# HoverGames_v2.net
KiCad netlist of a schematic drawn in EAGLE
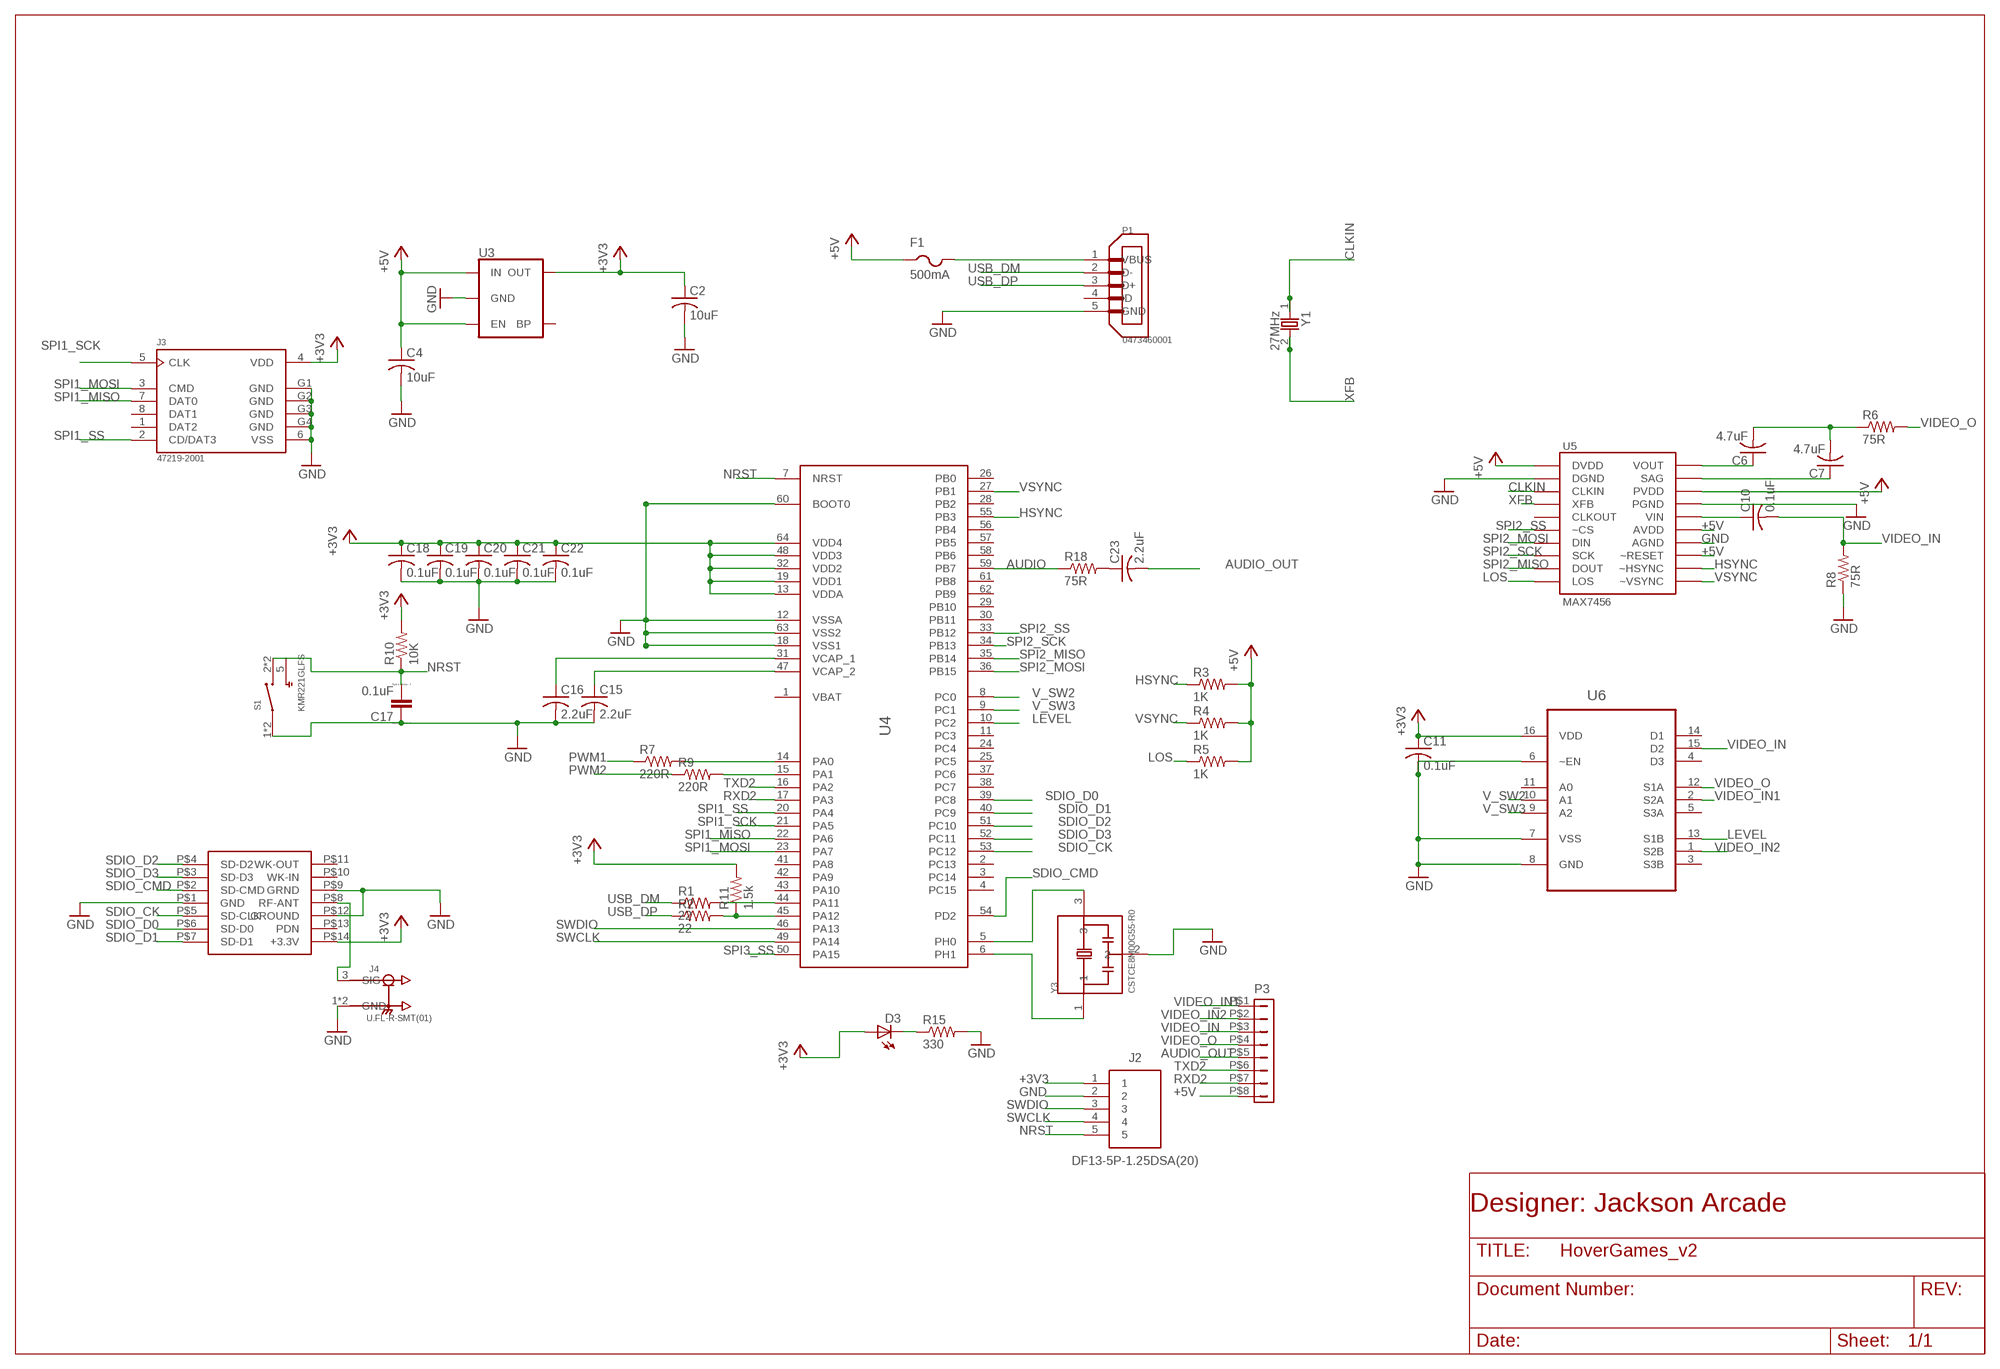
[diagram p0: schematic, sheet 1]

(export (version "E")
  (design (tool "Eeschema 10.0.6"))
  (components
    (comp (ref "C2")
      (value "10uF")
      (footprint "eagle-import:C0402")
      (libsource (lib "eagle-import") (part "C-USC0402"))
    )
    (comp (ref "C4")
      (value "10uF")
      (footprint "eagle-import:C0402")
      (libsource (lib "eagle-import") (part "C-USC0402"))
    )
    (comp (ref "C6")
      (value "4.7uF")
      (footprint "eagle-import:C0402")
      (libsource (lib "eagle-import") (part "C-USC0402"))
    )
    (comp (ref "C7")
      (value "4.7uF")
      (footprint "eagle-import:C0402")
      (libsource (lib "eagle-import") (part "C-USC0402"))
    )
    (comp (ref "C10")
      (value "0.1uF")
      (footprint "eagle-import:C0402")
      (libsource (lib "eagle-import") (part "resistor_348_C-USC0402"))
    )
    (comp (ref "C11")
      (value "0.1uF")
      (footprint "eagle-import:C0402")
      (libsource (lib "eagle-import") (part "C-USC0402"))
    )
    (comp (ref "C15")
      (value "2.2uF")
      (footprint "eagle-import:C0603")
      (libsource (lib "eagle-import") (part "C-USC0603"))
    )
    (comp (ref "C16")
      (value "2.2uF")
      (footprint "eagle-import:C0603")
      (libsource (lib "eagle-import") (part "C-USC0603"))
    )
    (comp (ref "C17")
      (value "0.1uF")
      (footprint "eagle-import:C0402")
      (libsource (lib "eagle-import") (part "CC0402"))
    )
    (comp (ref "C18")
      (value "0.1uF")
      (footprint "eagle-import:C0402")
      (libsource (lib "eagle-import") (part "C-USC0402"))
    )
    (comp (ref "C19")
      (value "0.1uF")
      (footprint "eagle-import:C0402")
      (libsource (lib "eagle-import") (part "C-USC0402"))
    )
    (comp (ref "C20")
      (value "0.1uF")
      (footprint "eagle-import:C0402")
      (libsource (lib "eagle-import") (part "C-USC0402"))
    )
    (comp (ref "C21")
      (value "0.1uF")
      (footprint "eagle-import:C0402")
      (libsource (lib "eagle-import") (part "C-USC0402"))
    )
    (comp (ref "C22")
      (value "0.1uF")
      (footprint "eagle-import:C0402")
      (libsource (lib "eagle-import") (part "C-USC0402"))
    )
    (comp (ref "C23")
      (value "2.2uF")
      (footprint "eagle-import:C0603")
      (libsource (lib "eagle-import") (part "C-USC0603"))
    )
    (comp (ref "D3")
      (value "LEDCHIP-LED0603")
      (footprint "eagle-import:CHIP-LED0603")
      (libsource (lib "eagle-import") (part "LEDCHIP-LED0603"))
    )
    (comp (ref "F1")
      (value "500mA")
      (footprint "eagle-import:R1206")
      (libsource (lib "eagle-import") (part "PTCFUSE-1206"))
    )
    (comp (ref "J2")
      (value "DF13-5P-1.25DSA(20)")
      (footprint "eagle-import:SHDR5W43P0X125_1X5_790X340X460")
      (fields (field (name "RS_PART_NUMBER") "5037912P"))
      (libsource (lib "eagle-import") (part "DF13-5P-1.25DSA(20)"))
    )
    (comp (ref "J3")
      (value "47219-2001")
      (footprint "eagle-import:MOLEX_47219-2001")
      (fields (field (name "MF") "Molex"))
      (libsource (lib "eagle-import") (part "47219-2001"))
    )
    (comp (ref "J4")
      (value "U.FL-R-SMT(01)")
      (footprint "eagle-import:HRS_U.FL-R-SMT(01)")
      (fields (field (name "MF") "Hirose"))
      (libsource (lib "eagle-import") (part "U.FL-R-SMT(01)"))
    )
    (comp (ref "P1")
      (value "0473460001")
      (footprint "eagle-import:MOLEX_0473460001")
      (fields (field (name "MF") "Weidmuller"))
      (libsource (lib "eagle-import") (part "0473460001"))
    )
    (comp (ref "P3")
      (value "DF13-8P-1.25DSA")
      (footprint "eagle-import:DF13-8P-1.25DSA")
      (libsource (lib "eagle-import") (part "DF13-8P-1.25DSA"))
    )
    (comp (ref "R1")
      (value "22")
      (footprint "eagle-import:R0402")
      (libsource (lib "eagle-import") (part "R-US_R0402"))
    )
    (comp (ref "R2")
      (value "22")
      (footprint "eagle-import:R0402")
      (libsource (lib "eagle-import") (part "R-US_R0402"))
    )
    (comp (ref "R3")
      (value "1K")
      (footprint "eagle-import:R0402")
      (libsource (lib "eagle-import") (part "R-US_R0402"))
    )
    (comp (ref "R4")
      (value "1K")
      (footprint "eagle-import:R0402")
      (libsource (lib "eagle-import") (part "R-US_R0402"))
    )
    (comp (ref "R5")
      (value "1K")
      (footprint "eagle-import:R0402")
      (libsource (lib "eagle-import") (part "R-US_R0402"))
    )
    (comp (ref "R6")
      (value "75R")
      (footprint "eagle-import:R0402")
      (libsource (lib "eagle-import") (part "R-US_R0402"))
    )
    (comp (ref "R7")
      (value "220R")
      (footprint "eagle-import:R0402")
      (libsource (lib "eagle-import") (part "R-US_R0402"))
    )
    (comp (ref "R8")
      (value "75R")
      (footprint "eagle-import:R0402")
      (libsource (lib "eagle-import") (part "resistor_348_R-US_R0402"))
    )
    (comp (ref "R9")
      (value "220R")
      (footprint "eagle-import:R0402")
      (libsource (lib "eagle-import") (part "R-US_R0402"))
    )
    (comp (ref "R10")
      (value "10K")
      (footprint "eagle-import:R0402")
      (libsource (lib "eagle-import") (part "R-US_R0402"))
    )
    (comp (ref "R11")
      (value "1.5k")
      (footprint "eagle-import:R0402")
      (libsource (lib "eagle-import") (part "R-US_R0402"))
    )
    (comp (ref "R15")
      (value "330")
      (footprint "eagle-import:R0402")
      (libsource (lib "eagle-import") (part "R-US_R0402"))
    )
    (comp (ref "R18")
      (value "75R")
      (footprint "eagle-import:R0402")
      (libsource (lib "eagle-import") (part "R-US_R0402"))
    )
    (comp (ref "S1")
      (value "KMR221GLFS")
      (footprint "eagle-import:SW_KMR221GLFS")
      (fields (field (name "MF") "C&K Components"))
      (libsource (lib "eagle-import") (part "KMR221GLFS"))
    )
    (comp (ref "U3")
      (value "V_REG_SPX3819-SOT23-5")
      (footprint "eagle-import:SOT23-5")
      (libsource (lib "eagle-import") (part "V_REG_SPX3819-SOT23-5"))
    )
    (comp (ref "U4")
      (value "STM32F405XXSTM32F405XX")
      (footprint "eagle-import:LQFP64")
      (libsource (lib "eagle-import") (part "STM32F405XXSTM32F405XX"))
    )
    (comp (ref "U5")
      (value "MAX7456")
      (footprint "eagle-import:TSSOP28")
      (libsource (lib "eagle-import") (part "MAX7456"))
    )
    (comp (ref "U6")
      (value "ADG733BRUZ")
      (footprint "eagle-import:SOP65P640X120-16N")
      (libsource (lib "eagle-import") (part "ADG733BRUZ"))
    )
    (comp (ref "U7")
      (value "88W8801")
      (footprint "eagle-import:88W8801")
      (libsource (lib "eagle-import") (part "88W8801"))
    )
    (comp (ref "Y1")
      (value "27MHz")
      (footprint "eagle-import:XTAL500X320X130N")
      (fields (field (name "MF") "Abracon") (field (name "MP") "ABM3-27.000MHZ-B2-T"))
      (libsource (lib "eagle-import") (part "ABM3-27.000MHZ-B2-T"))
    )
    (comp (ref "Y3")
      (value "CSTCE8M00G55-R0")
      (footprint "eagle-import:OSC_CSTCE8M00G55-R0")
      (fields (field (name "MF") "Murata"))
      (libsource (lib "eagle-import") (part "CSTCE8M00G55-R0"))
    )
  )
  (nets
    (net (code "1") (name "+3V3") (class "Default")
      (node (ref "C11") (pin "1") (pinfunction "1_1") (pintype "passive"))
      (node (ref "C18") (pin "1") (pinfunction "1_1") (pintype "passive"))
      (node (ref "C19") (pin "1") (pinfunction "1_1") (pintype "passive"))
      (node (ref "C2") (pin "1") (pinfunction "1_1") (pintype "passive"))
      (node (ref "C20") (pin "1") (pinfunction "1_1") (pintype "passive"))
      (node (ref "C21") (pin "1") (pinfunction "1_1") (pintype "passive"))
      (node (ref "C22") (pin "1") (pinfunction "1_1") (pintype "passive"))
      (node (ref "D3") (pin "A") (pinfunction "A_A") (pintype "passive"))
      (node (ref "J2") (pin "1") (pinfunction "1_1") (pintype "passive"))
      (node (ref "J3") (pin "4") (pinfunction "VDD_4") (pintype "power_in"))
      (node (ref "R10") (pin "2") (pinfunction "2_2") (pintype "passive"))
      (node (ref "R11") (pin "2") (pinfunction "2_2") (pintype "passive"))
      (node (ref "U3") (pin "5") (pinfunction "OUT_5") (pintype "passive"))
      (node (ref "U4") (pin "13") (pinfunction "VDDA_13") (pintype "power_in"))
      (node (ref "U4") (pin "19") (pinfunction "VDD1_19") (pintype "power_in"))
      (node (ref "U4") (pin "32") (pinfunction "VDD2_32") (pintype "power_in"))
      (node (ref "U4") (pin "48") (pinfunction "VDD3_48") (pintype "power_in"))
      (node (ref "U4") (pin "64") (pinfunction "VDD4_64") (pintype "power_in"))
      (node (ref "U6") (pin "16") (pinfunction "VDD_16") (pintype "power_in"))
      (node (ref "U7") (pin "P$14") (pinfunction "+3.3V_P$14") (pintype "bidirectional"))
    )
    (net (code "2") (name "+5V") (class "Default")
      (node (ref "C4") (pin "1") (pinfunction "1_1") (pintype "passive"))
      (node (ref "F1") (pin "1") (pinfunction "1_1") (pintype "passive"))
      (node (ref "P3") (pin "P$8") (pinfunction "8_P$8") (pintype "passive"))
      (node (ref "R3") (pin "2") (pinfunction "2_2") (pintype "passive"))
      (node (ref "R4") (pin "2") (pinfunction "2_2") (pintype "passive"))
      (node (ref "R5") (pin "2") (pinfunction "2_2") (pintype "passive"))
      (node (ref "U3") (pin "1") (pinfunction "IN_1") (pintype "input"))
      (node (ref "U3") (pin "3") (pinfunction "EN_3") (pintype "input"))
      (node (ref "U5") (pin "19") (pinfunction "~{RESET}_19") (pintype "bidirectional"))
      (node (ref "U5") (pin "21") (pinfunction "AVDD_21") (pintype "bidirectional"))
      (node (ref "U5") (pin "24") (pinfunction "PVDD_24") (pintype "bidirectional"))
      (node (ref "U5") (pin "3") (pinfunction "DVDD_3") (pintype "bidirectional"))
    )
    (net (code "3") (name "/AUDIO") (class "Default")
      (node (ref "R18") (pin "1") (pinfunction "1_1") (pintype "passive"))
      (node (ref "U4") (pin "59") (pinfunction "PB7_59") (pintype "bidirectional"))
    )
    (net (code "4") (name "/AUDIO_OUT") (class "Default")
      (node (ref "C23") (pin "2") (pinfunction "2_2") (pintype "passive"))
      (node (ref "P3") (pin "P$5") (pinfunction "5_P$5") (pintype "passive"))
    )
    (net (code "5") (name "/CLKIN") (class "Default")
      (node (ref "U5") (pin "5") (pinfunction "CLKIN_5") (pintype "bidirectional"))
      (node (ref "Y1") (pin "1") (pinfunction "1_1") (pintype "passive"))
    )
    (net (code "6") (name "/HSYNC") (class "Default")
      (node (ref "R3") (pin "1") (pinfunction "1_1") (pintype "passive"))
      (node (ref "U4") (pin "55") (pinfunction "PB3_55") (pintype "bidirectional"))
      (node (ref "U5") (pin "18") (pinfunction "~{HSYNC}_18") (pintype "bidirectional"))
    )
    (net (code "7") (name "/LEVEL") (class "Default")
      (node (ref "U4") (pin "10") (pinfunction "PC2_10") (pintype "bidirectional"))
      (node (ref "U6") (pin "13") (pinfunction "S1B_13") (pintype "bidirectional"))
    )
    (net (code "8") (name "/LOS") (class "Default")
      (node (ref "R5") (pin "1") (pinfunction "1_1") (pintype "passive"))
      (node (ref "U5") (pin "12") (pinfunction "LOS_12") (pintype "bidirectional"))
    )
    (net (code "9") (name "/NRST") (class "Default")
      (node (ref "C17") (pin "2") (pinfunction "2_2") (pintype "passive"))
      (node (ref "J2") (pin "5") (pinfunction "5_5") (pintype "passive"))
      (node (ref "R10") (pin "1") (pinfunction "1_1") (pintype "passive"))
      (node (ref "S1") (pin "2") (pinfunction "3_2") (pintype "passive"))
      (node (ref "S1") (pin "3") (pinfunction "3_3") (pintype "passive"))
      (node (ref "U4") (pin "7") (pinfunction "NRST_7") (pintype "bidirectional"))
    )
    (net (code "10") (name "/PWM1") (class "Default")
      (node (ref "R7") (pin "1") (pinfunction "1_1") (pintype "passive"))
    )
    (net (code "11") (name "/PWM2") (class "Default")
      (node (ref "R9") (pin "1") (pinfunction "1_1") (pintype "passive"))
    )
    (net (code "12") (name "/RXD2") (class "Default")
      (node (ref "P3") (pin "P$7") (pinfunction "7_P$7") (pintype "passive"))
      (node (ref "U4") (pin "17") (pinfunction "PA3_17") (pintype "bidirectional"))
    )
    (net (code "13") (name "/SDIO_CK") (class "Default")
      (node (ref "U4") (pin "53") (pinfunction "PC12_53") (pintype "bidirectional"))
      (node (ref "U7") (pin "P$5") (pinfunction "SD-CLK_P$5") (pintype "bidirectional"))
    )
    (net (code "14") (name "/SDIO_CMD") (class "Default")
      (node (ref "U4") (pin "54") (pinfunction "PD2_54") (pintype "bidirectional"))
      (node (ref "U7") (pin "P$2") (pinfunction "SD-CMD_P$2") (pintype "bidirectional"))
    )
    (net (code "15") (name "/SDIO_D0") (class "Default")
      (node (ref "U4") (pin "39") (pinfunction "PC8_39") (pintype "bidirectional"))
      (node (ref "U7") (pin "P$6") (pinfunction "SD-D0_P$6") (pintype "bidirectional"))
    )
    (net (code "16") (name "/SDIO_D1") (class "Default")
      (node (ref "U4") (pin "40") (pinfunction "PC9_40") (pintype "bidirectional"))
      (node (ref "U7") (pin "P$7") (pinfunction "SD-D1_P$7") (pintype "bidirectional"))
    )
    (net (code "17") (name "/SDIO_D2") (class "Default")
      (node (ref "U4") (pin "51") (pinfunction "PC10_51") (pintype "bidirectional"))
      (node (ref "U7") (pin "P$4") (pinfunction "SD-D2_P$4") (pintype "bidirectional"))
    )
    (net (code "18") (name "/SDIO_D3") (class "Default")
      (node (ref "U4") (pin "52") (pinfunction "PC11_52") (pintype "bidirectional"))
      (node (ref "U7") (pin "P$3") (pinfunction "SD-D3_P$3") (pintype "bidirectional"))
    )
    (net (code "19") (name "/SPI1_MISO") (class "Default")
      (node (ref "J3") (pin "7") (pinfunction "DAT0_7") (pintype "bidirectional"))
      (node (ref "U4") (pin "22") (pinfunction "PA6_22") (pintype "bidirectional"))
    )
    (net (code "20") (name "/SPI1_MOSI") (class "Default")
      (node (ref "J3") (pin "3") (pinfunction "CMD_3") (pintype "bidirectional"))
      (node (ref "U4") (pin "23") (pinfunction "PA7_23") (pintype "bidirectional"))
    )
    (net (code "21") (name "/SPI1_SCK") (class "Default")
      (node (ref "J3") (pin "5") (pinfunction "CLK_5") (pintype "input"))
      (node (ref "U4") (pin "21") (pinfunction "PA5_21") (pintype "bidirectional"))
    )
    (net (code "22") (name "/SPI1_SS") (class "Default")
      (node (ref "J3") (pin "2") (pinfunction "CD/DAT3_2") (pintype "bidirectional"))
      (node (ref "U4") (pin "20") (pinfunction "PA4_20") (pintype "bidirectional"))
    )
    (net (code "23") (name "/SPI2_MISO") (class "Default")
      (node (ref "U4") (pin "35") (pinfunction "PB14_35") (pintype "bidirectional"))
      (node (ref "U5") (pin "11") (pinfunction "DOUT_11") (pintype "bidirectional"))
    )
    (net (code "24") (name "/SPI2_MOSI") (class "Default")
      (node (ref "U4") (pin "36") (pinfunction "PB15_36") (pintype "bidirectional"))
      (node (ref "U5") (pin "9") (pinfunction "DIN_9") (pintype "bidirectional"))
    )
    (net (code "25") (name "/SPI2_SCK") (class "Default")
      (node (ref "U4") (pin "34") (pinfunction "PB13_34") (pintype "bidirectional"))
      (node (ref "U5") (pin "10") (pinfunction "SCK_10") (pintype "bidirectional"))
    )
    (net (code "26") (name "/SPI2_SS") (class "Default")
      (node (ref "U4") (pin "33") (pinfunction "PB12_33") (pintype "bidirectional"))
      (node (ref "U5") (pin "8") (pinfunction "~{CS}_8") (pintype "bidirectional"))
    )
    (net (code "27") (name "/SPI3_SS") (class "Default")
      (node (ref "U4") (pin "50") (pinfunction "PA15_50") (pintype "bidirectional"))
    )
    (net (code "28") (name "/SWCLK") (class "Default")
      (node (ref "J2") (pin "4") (pinfunction "4_4") (pintype "passive"))
      (node (ref "U4") (pin "49") (pinfunction "PA14_49") (pintype "bidirectional"))
    )
    (net (code "29") (name "/SWDIO") (class "Default")
      (node (ref "J2") (pin "3") (pinfunction "3_3") (pintype "passive"))
      (node (ref "U4") (pin "46") (pinfunction "PA13_46") (pintype "bidirectional"))
    )
    (net (code "30") (name "/TXD2") (class "Default")
      (node (ref "P3") (pin "P$6") (pinfunction "6_P$6") (pintype "passive"))
      (node (ref "U4") (pin "16") (pinfunction "PA2_16") (pintype "bidirectional"))
    )
    (net (code "31") (name "/USB_DM") (class "Default")
      (node (ref "P1") (pin "2") (pinfunction "D-_2") (pintype "bidirectional"))
      (node (ref "R1") (pin "1") (pinfunction "1_1") (pintype "passive"))
    )
    (net (code "32") (name "/USB_DP") (class "Default")
      (node (ref "P1") (pin "3") (pinfunction "D+_3") (pintype "bidirectional"))
      (node (ref "R2") (pin "1") (pinfunction "1_1") (pintype "passive"))
    )
    (net (code "33") (name "/VBAT") (class "Default")
      (node (ref "U4") (pin "1") (pinfunction "VBAT_1") (pintype "power_in"))
    )
    (net (code "34") (name "/VIDEO_IN") (class "Default")
      (node (ref "C10") (pin "2") (pinfunction "2_2") (pintype "passive"))
      (node (ref "P3") (pin "P$3") (pinfunction "3_P$3") (pintype "passive"))
      (node (ref "R8") (pin "2") (pinfunction "2_2") (pintype "passive"))
      (node (ref "U6") (pin "15") (pinfunction "D2_15") (pintype "bidirectional"))
    )
    (net (code "35") (name "/VIDEO_IN1") (class "Default")
      (node (ref "P3") (pin "P$1") (pinfunction "1_P$1") (pintype "passive"))
      (node (ref "U6") (pin "2") (pinfunction "S2A_2") (pintype "bidirectional"))
    )
    (net (code "36") (name "/VIDEO_IN2") (class "Default")
      (node (ref "P3") (pin "P$2") (pinfunction "2_P$2") (pintype "passive"))
      (node (ref "U6") (pin "1") (pinfunction "S2B_1") (pintype "bidirectional"))
    )
    (net (code "37") (name "/VIDEO_O") (class "Default")
      (node (ref "P3") (pin "P$4") (pinfunction "4_P$4") (pintype "passive"))
      (node (ref "R6") (pin "2") (pinfunction "2_2") (pintype "passive"))
      (node (ref "U6") (pin "12") (pinfunction "S1A_12") (pintype "bidirectional"))
    )
    (net (code "38") (name "/VSYNC") (class "Default")
      (node (ref "R4") (pin "1") (pinfunction "1_1") (pintype "passive"))
      (node (ref "U4") (pin "27") (pinfunction "PB1_27") (pintype "bidirectional"))
      (node (ref "U5") (pin "17") (pinfunction "~{VSYNC}_17") (pintype "bidirectional"))
    )
    (net (code "39") (name "/V_SW2") (class "Default")
      (node (ref "U4") (pin "8") (pinfunction "PC0_8") (pintype "bidirectional"))
      (node (ref "U6") (pin "10") (pinfunction "A1_10") (pintype "input"))
    )
    (net (code "40") (name "/V_SW3") (class "Default")
      (node (ref "U4") (pin "9") (pinfunction "PC1_9") (pintype "bidirectional"))
      (node (ref "U6") (pin "9") (pinfunction "A2_9") (pintype "input"))
    )
    (net (code "41") (name "/XFB") (class "Default")
      (node (ref "U5") (pin "6") (pinfunction "XFB_6") (pintype "bidirectional"))
      (node (ref "Y1") (pin "2") (pinfunction "2_2") (pintype "passive"))
    )
    (net (code "42") (name "GND") (class "Default")
      (node (ref "C11") (pin "2") (pinfunction "2_2") (pintype "passive"))
      (node (ref "C15") (pin "2") (pinfunction "2_2") (pintype "passive"))
      (node (ref "C16") (pin "2") (pinfunction "2_2") (pintype "passive"))
      (node (ref "C17") (pin "1") (pinfunction "1_1") (pintype "passive"))
      (node (ref "C18") (pin "2") (pinfunction "2_2") (pintype "passive"))
      (node (ref "C19") (pin "2") (pinfunction "2_2") (pintype "passive"))
      (node (ref "C2") (pin "2") (pinfunction "2_2") (pintype "passive"))
      (node (ref "C20") (pin "2") (pinfunction "2_2") (pintype "passive"))
      (node (ref "C21") (pin "2") (pinfunction "2_2") (pintype "passive"))
      (node (ref "C22") (pin "2") (pinfunction "2_2") (pintype "passive"))
      (node (ref "C4") (pin "2") (pinfunction "2_2") (pintype "passive"))
      (node (ref "J2") (pin "2") (pinfunction "2_2") (pintype "passive"))
      (node (ref "J3") (pin "6") (pinfunction "VSS_6") (pintype "power_in"))
      (node (ref "J3") (pin "G1") (pinfunction "GND_G1") (pintype "power_in"))
      (node (ref "J3") (pin "G2") (pinfunction "GND_G2") (pintype "power_in"))
      (node (ref "J3") (pin "G3") (pinfunction "GND_G3") (pintype "power_in"))
      (node (ref "J3") (pin "G4") (pinfunction "GND_G4") (pintype "power_in"))
      (node (ref "J4") (pin "1") (pinfunction "GND_1") (pintype "passive"))
      (node (ref "J4") (pin "2") (pinfunction "GND_2") (pintype "passive"))
      (node (ref "P1") (pin "5") (pinfunction "GND_5") (pintype "passive"))
      (node (ref "R15") (pin "2") (pinfunction "2_2") (pintype "passive"))
      (node (ref "R8") (pin "1") (pinfunction "1_1") (pintype "passive"))
      (node (ref "S1") (pin "1") (pinfunction "1_1") (pintype "passive"))
      (node (ref "S1") (pin "4") (pinfunction "1_4") (pintype "passive"))
      (node (ref "U3") (pin "2") (pinfunction "GND_2") (pintype "input"))
      (node (ref "U4") (pin "12") (pinfunction "VSSA_12") (pintype "power_in"))
      (node (ref "U4") (pin "18") (pinfunction "VSS1_18") (pintype "power_in"))
      (node (ref "U4") (pin "60") (pinfunction "BOOT0_60") (pintype "bidirectional"))
      (node (ref "U4") (pin "63") (pinfunction "VSS2_63") (pintype "power_in"))
      (node (ref "U5") (pin "20") (pinfunction "AGND_20") (pintype "bidirectional"))
      (node (ref "U5") (pin "23") (pinfunction "PGND_23") (pintype "bidirectional"))
      (node (ref "U5") (pin "4") (pinfunction "DGND_4") (pintype "bidirectional"))
      (node (ref "U6") (pin "6") (pinfunction "~{EN}_6") (pintype "input"))
      (node (ref "U6") (pin "7") (pinfunction "VSS_7") (pintype "power_in"))
      (node (ref "U6") (pin "8") (pinfunction "GND_8") (pintype "passive"))
      (node (ref "U7") (pin "P$1") (pinfunction "GND_P$1") (pintype "bidirectional"))
      (node (ref "U7") (pin "P$12") (pinfunction "GROUND_P$12") (pintype "bidirectional"))
      (node (ref "U7") (pin "P$9") (pinfunction "GRND_P$9") (pintype "bidirectional"))
      (node (ref "Y3") (pin "2") (pinfunction "2_2") (pintype "power_in"))
    )
    (net (code "43") (name "Net-(C6-Pad2)") (class "Default")
      (node (ref "C6") (pin "2") (pinfunction "2_2") (pintype "passive"))
      (node (ref "C7") (pin "2") (pinfunction "2_2") (pintype "passive"))
      (node (ref "R6") (pin "1") (pinfunction "1_1") (pintype "passive"))
    )
    (net (code "44") (name "Net-(C23-Pad1)") (class "Default")
      (node (ref "C23") (pin "1") (pinfunction "1_1") (pintype "passive"))
      (node (ref "R18") (pin "2") (pinfunction "2_2") (pintype "passive"))
    )
    (net (code "45") (name "Net-(D3-PadC)") (class "Default")
      (node (ref "D3") (pin "C") (pinfunction "C_C") (pintype "passive"))
      (node (ref "R15") (pin "1") (pinfunction "1_1") (pintype "passive"))
    )
    (net (code "46") (name "Net-(J4-SIG)") (class "Default")
      (node (ref "J4") (pin "3") (pinfunction "SIG_3") (pintype "passive"))
      (node (ref "U7") (pin "P$8") (pinfunction "RF-ANT_P$8") (pintype "bidirectional"))
    )
    (net (code "47") (name "Net-(P1-VBUS)") (class "Default")
      (node (ref "F1") (pin "2") (pinfunction "2_2") (pintype "passive"))
      (node (ref "P1") (pin "1") (pinfunction "VBUS_1") (pintype "power_in"))
    )
    (net (code "48") (name "Net-(U4-PA0)") (class "Default")
      (node (ref "R7") (pin "2") (pinfunction "2_2") (pintype "passive"))
      (node (ref "U4") (pin "14") (pinfunction "PA0_14") (pintype "bidirectional"))
    )
    (net (code "49") (name "Net-(U4-PA1)") (class "Default")
      (node (ref "R9") (pin "2") (pinfunction "2_2") (pintype "passive"))
      (node (ref "U4") (pin "15") (pinfunction "PA1_15") (pintype "bidirectional"))
    )
    (net (code "50") (name "Net-(U4-PA11)") (class "Default")
      (node (ref "R1") (pin "2") (pinfunction "2_2") (pintype "passive"))
      (node (ref "U4") (pin "44") (pinfunction "PA11_44") (pintype "bidirectional"))
    )
    (net (code "51") (name "Net-(U4-PA12)") (class "Default")
      (node (ref "R11") (pin "1") (pinfunction "1_1") (pintype "passive"))
      (node (ref "R2") (pin "2") (pinfunction "2_2") (pintype "passive"))
      (node (ref "U4") (pin "45") (pinfunction "PA12_45") (pintype "bidirectional"))
    )
    (net (code "52") (name "Net-(U4-PH0)") (class "Default")
      (node (ref "U4") (pin "5") (pinfunction "PH0_5") (pintype "bidirectional"))
      (node (ref "Y3") (pin "3") (pinfunction "3_3") (pintype "passive"))
    )
    (net (code "53") (name "Net-(U4-PH1)") (class "Default")
      (node (ref "U4") (pin "6") (pinfunction "PH1_6") (pintype "bidirectional"))
      (node (ref "Y3") (pin "1") (pinfunction "1_1") (pintype "passive"))
    )
    (net (code "54") (name "Net-(U4-VCAP_1)") (class "Default")
      (node (ref "C16") (pin "1") (pinfunction "1_1") (pintype "passive"))
      (node (ref "U4") (pin "31") (pinfunction "VCAP_1_31") (pintype "power_in"))
    )
    (net (code "55") (name "Net-(U4-VCAP_2)") (class "Default")
      (node (ref "C15") (pin "1") (pinfunction "1_1") (pintype "passive"))
      (node (ref "U4") (pin "47") (pinfunction "VCAP_2_47") (pintype "power_in"))
    )
    (net (code "56") (name "Net-(U5-SAG)") (class "Default")
      (node (ref "C7") (pin "1") (pinfunction "1_1") (pintype "passive"))
      (node (ref "U5") (pin "25") (pinfunction "SAG_25") (pintype "bidirectional"))
    )
    (net (code "57") (name "Net-(U5-VIN)") (class "Default")
      (node (ref "C10") (pin "1") (pinfunction "1_1") (pintype "passive"))
      (node (ref "U5") (pin "22") (pinfunction "VIN_22") (pintype "bidirectional"))
    )
    (net (code "58") (name "Net-(U5-VOUT)") (class "Default")
      (node (ref "C6") (pin "1") (pinfunction "1_1") (pintype "passive"))
      (node (ref "U5") (pin "26") (pinfunction "VOUT_26") (pintype "bidirectional"))
    )
    (net (code "59") (name "unconnected-(J3-DAT1-Pad8)") (class "Default")
      (node (ref "J3") (pin "8") (pinfunction "DAT1_8") (pintype "bidirectional"))
    )
    (net (code "60") (name "unconnected-(J3-DAT2-Pad1)") (class "Default")
      (node (ref "J3") (pin "1") (pinfunction "DAT2_1") (pintype "bidirectional"))
    )
    (net (code "61") (name "unconnected-(P1-ID-Pad4)") (class "Default")
      (node (ref "P1") (pin "4") (pinfunction "ID_4") (pintype "bidirectional"))
    )
    (net (code "62") (name "unconnected-(S1-Pad5)") (class "Default")
      (node (ref "S1") (pin "5") (pinfunction "5_5") (pintype "passive"))
    )
    (net (code "63") (name "unconnected-(U3-BP-Pad4)") (class "Default")
      (node (ref "U3") (pin "4") (pinfunction "BP_4") (pintype "input"))
    )
    (net (code "64") (name "unconnected-(U4-PA8-Pad41)") (class "Default")
      (node (ref "U4") (pin "41") (pinfunction "PA8_41") (pintype "bidirectional"))
    )
    (net (code "65") (name "unconnected-(U4-PA9-Pad42)") (class "Default")
      (node (ref "U4") (pin "42") (pinfunction "PA9_42") (pintype "bidirectional"))
    )
    (net (code "66") (name "unconnected-(U4-PA10-Pad43)") (class "Default")
      (node (ref "U4") (pin "43") (pinfunction "PA10_43") (pintype "bidirectional"))
    )
    (net (code "67") (name "unconnected-(U4-PB0-Pad26)") (class "Default")
      (node (ref "U4") (pin "26") (pinfunction "PB0_26") (pintype "bidirectional"))
    )
    (net (code "68") (name "unconnected-(U4-PB2-Pad28)") (class "Default")
      (node (ref "U4") (pin "28") (pinfunction "PB2_28") (pintype "bidirectional"))
    )
    (net (code "69") (name "unconnected-(U4-PB4-Pad56)") (class "Default")
      (node (ref "U4") (pin "56") (pinfunction "PB4_56") (pintype "bidirectional"))
    )
    (net (code "70") (name "unconnected-(U4-PB5-Pad57)") (class "Default")
      (node (ref "U4") (pin "57") (pinfunction "PB5_57") (pintype "bidirectional"))
    )
    (net (code "71") (name "unconnected-(U4-PB6-Pad58)") (class "Default")
      (node (ref "U4") (pin "58") (pinfunction "PB6_58") (pintype "bidirectional"))
    )
    (net (code "72") (name "unconnected-(U4-PB8-Pad61)") (class "Default")
      (node (ref "U4") (pin "61") (pinfunction "PB8_61") (pintype "bidirectional"))
    )
    (net (code "73") (name "unconnected-(U4-PB9-Pad62)") (class "Default")
      (node (ref "U4") (pin "62") (pinfunction "PB9_62") (pintype "bidirectional"))
    )
    (net (code "74") (name "unconnected-(U4-PB10-Pad29)") (class "Default")
      (node (ref "U4") (pin "29") (pinfunction "PB10_29") (pintype "bidirectional"))
    )
    (net (code "75") (name "unconnected-(U4-PB11-Pad30)") (class "Default")
      (node (ref "U4") (pin "30") (pinfunction "PB11_30") (pintype "bidirectional"))
    )
    (net (code "76") (name "unconnected-(U4-PC3-Pad11)") (class "Default")
      (node (ref "U4") (pin "11") (pinfunction "PC3_11") (pintype "bidirectional"))
    )
    (net (code "77") (name "unconnected-(U4-PC4-Pad24)") (class "Default")
      (node (ref "U4") (pin "24") (pinfunction "PC4_24") (pintype "bidirectional"))
    )
    (net (code "78") (name "unconnected-(U4-PC5-Pad25)") (class "Default")
      (node (ref "U4") (pin "25") (pinfunction "PC5_25") (pintype "bidirectional"))
    )
    (net (code "79") (name "unconnected-(U4-PC6-Pad37)") (class "Default")
      (node (ref "U4") (pin "37") (pinfunction "PC6_37") (pintype "bidirectional"))
    )
    (net (code "80") (name "unconnected-(U4-PC7-Pad38)") (class "Default")
      (node (ref "U4") (pin "38") (pinfunction "PC7_38") (pintype "bidirectional"))
    )
    (net (code "81") (name "unconnected-(U4-PC13-Pad2)") (class "Default")
      (node (ref "U4") (pin "2") (pinfunction "PC13_2") (pintype "bidirectional"))
    )
    (net (code "82") (name "unconnected-(U4-PC14-Pad3)") (class "Default")
      (node (ref "U4") (pin "3") (pinfunction "PC14_3") (pintype "bidirectional"))
    )
    (net (code "83") (name "unconnected-(U4-PC15-Pad4)") (class "Default")
      (node (ref "U4") (pin "4") (pinfunction "PC15_4") (pintype "bidirectional"))
    )
    (net (code "84") (name "unconnected-(U5-CLKOUT-Pad7)") (class "Default")
      (node (ref "U5") (pin "7") (pinfunction "CLKOUT_7") (pintype "bidirectional"))
    )
    (net (code "85") (name "unconnected-(U6-A0-Pad11)") (class "Default")
      (node (ref "U6") (pin "11") (pinfunction "A0_11") (pintype "input"))
    )
    (net (code "86") (name "unconnected-(U6-D1-Pad14)") (class "Default")
      (node (ref "U6") (pin "14") (pinfunction "D1_14") (pintype "bidirectional"))
    )
    (net (code "87") (name "unconnected-(U6-D3-Pad4)") (class "Default")
      (node (ref "U6") (pin "4") (pinfunction "D3_4") (pintype "bidirectional"))
    )
    (net (code "88") (name "unconnected-(U6-S3A-Pad5)") (class "Default")
      (node (ref "U6") (pin "5") (pinfunction "S3A_5") (pintype "bidirectional"))
    )
    (net (code "89") (name "unconnected-(U6-S3B-Pad3)") (class "Default")
      (node (ref "U6") (pin "3") (pinfunction "S3B_3") (pintype "bidirectional"))
    )
    (net (code "90") (name "unconnected-(U7-PDN-PadP$13)") (class "Default")
      (node (ref "U7") (pin "P$13") (pinfunction "PDN_P$13") (pintype "bidirectional"))
    )
    (net (code "91") (name "unconnected-(U7-WK-IN-PadP$10)") (class "Default")
      (node (ref "U7") (pin "P$10") (pinfunction "WK-IN_P$10") (pintype "bidirectional"))
    )
    (net (code "92") (name "unconnected-(U7-WK-OUT-PadP$11)") (class "Default")
      (node (ref "U7") (pin "P$11") (pinfunction "WK-OUT_P$11") (pintype "bidirectional"))
    )
  )
)
